# akabeacon_square_type2.net
KiCad netlist of a schematic drawn in EAGLE
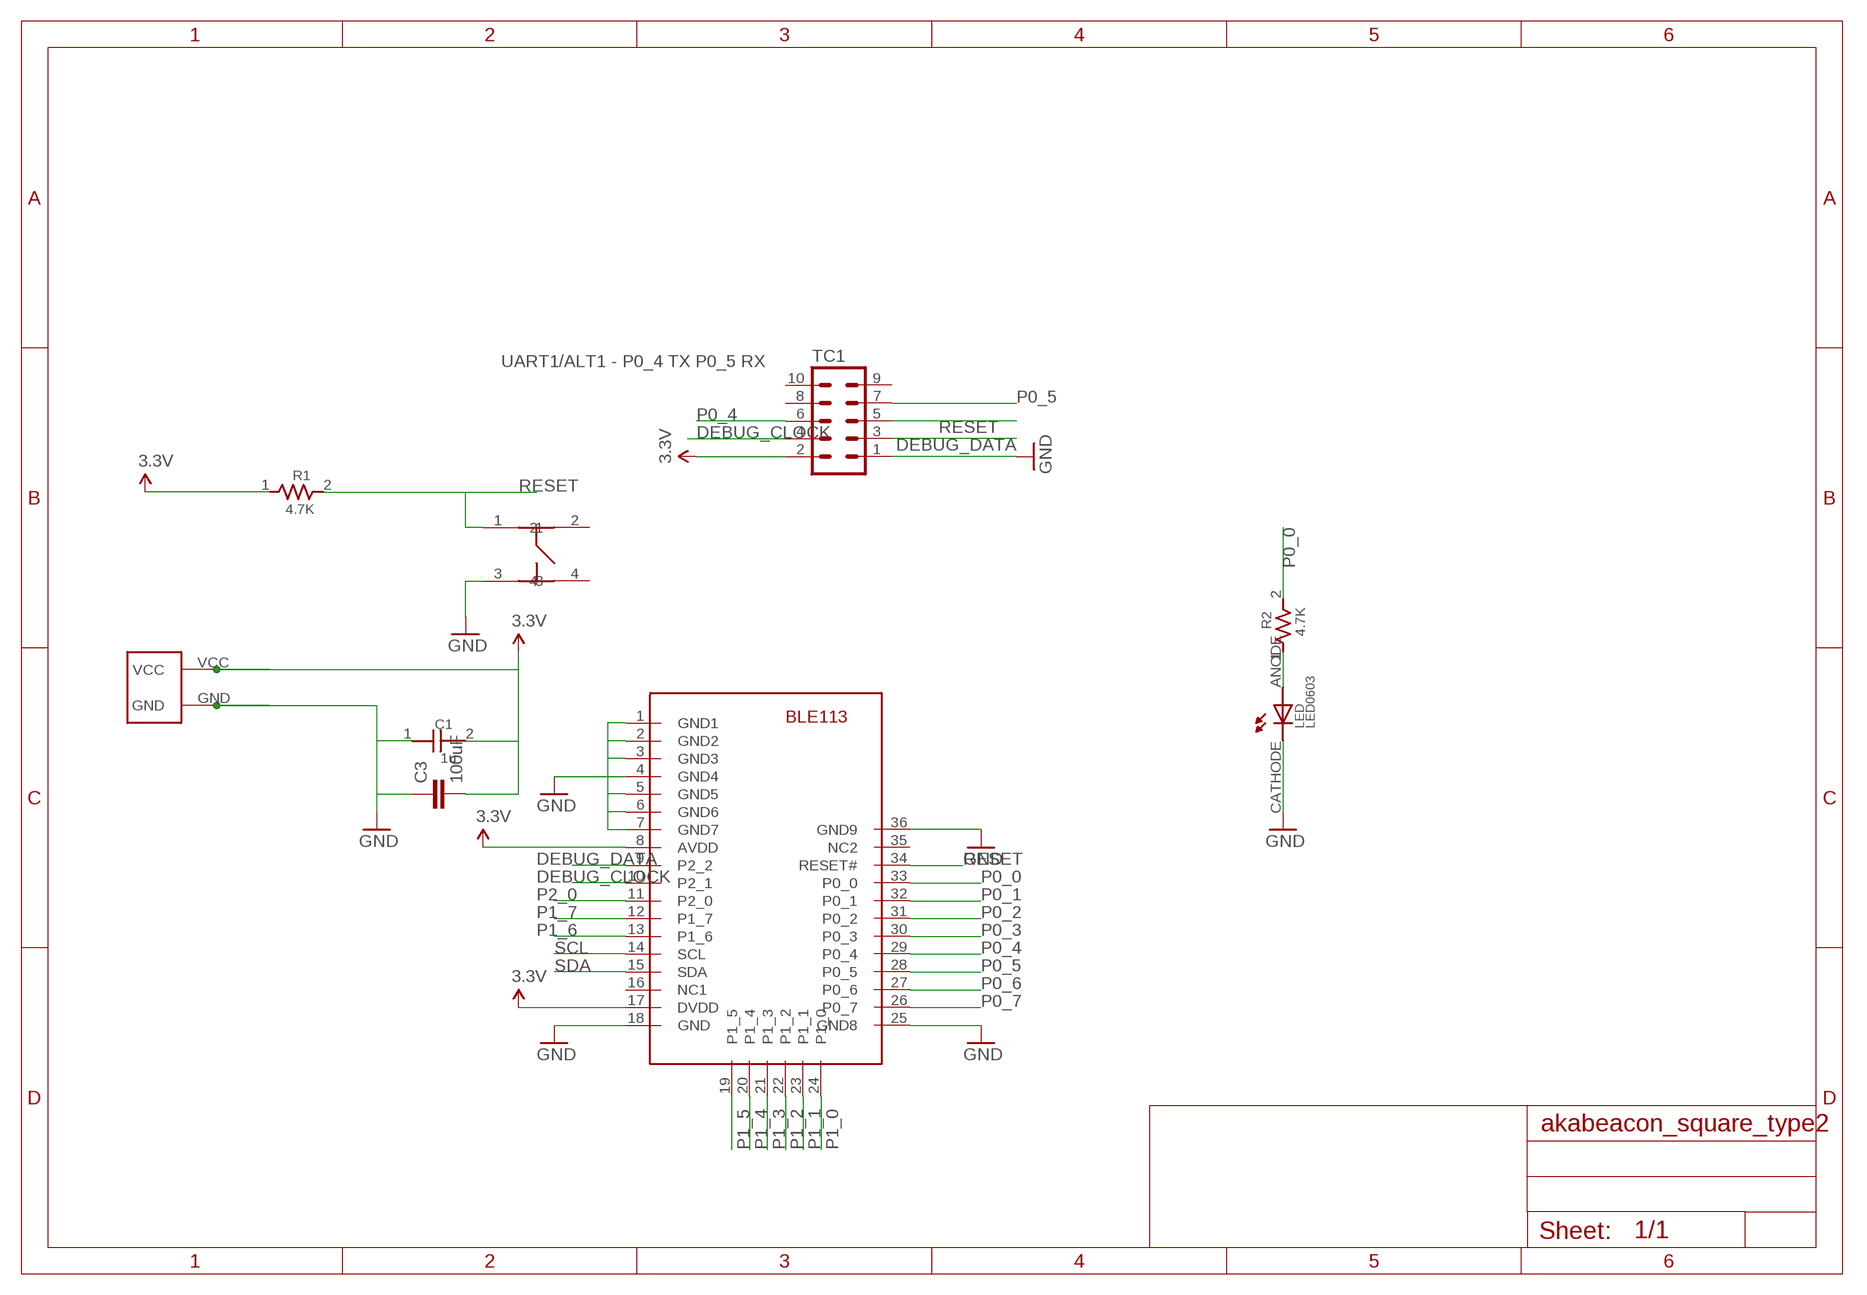
[diagram p0: schematic, sheet 1]

(export (version "E")
  (design (tool "Eeschema 10.0.6"))
  (components
    (comp (ref "C1")
      (value "1u")
      (footprint "eagle-import:0603")
      (libsource (lib "eagle-import") (part "CAPACITOR0603"))
    )
    (comp (ref "C3")
      (value "100uF")
      (footprint "eagle-import:1206")
      (libsource (lib "eagle-import") (part "10UF-6.3V-20%(1206)"))
    )
    (comp (ref "LED")
      (value "LED0603")
      (footprint "eagle-import:0603")
      (libsource (lib "eagle-import") (part "LED0603"))
    )
    (comp (ref "R1")
      (value "4.7K")
      (footprint "eagle-import:0603")
      (libsource (lib "eagle-import") (part "RESISTOR0603"))
    )
    (comp (ref "R2")
      (value "4.7K")
      (footprint "eagle-import:0603")
      (libsource (lib "eagle-import") (part "RESISTOR0603"))
    )
    (comp (ref "TC1")
      (value "TC2050-IDC-NL")
      (footprint "eagle-import:TC2050-IDC-NL")
      (libsource (lib "eagle-import") (part "TC2050-IDC-NL"))
    )
    (comp (ref "U$3")
      (value "SQUARE-TYPE2-TC2050")
      (footprint "eagle-import:SQUARE-TYPE2-TC2050")
      (libsource (lib "eagle-import") (part "SQUARE-TYPE2-TC2050"))
    )
    (comp (ref "U$5")
      (value "BLE113")
      (footprint "eagle-import:BLE113")
      (libsource (lib "eagle-import") (part "BLE113"))
    )
    (comp (ref "U$6")
      (value "SWICTH-4P(KMR2)")
      (footprint "eagle-import:SWITCH-4P(KMR2)")
      (libsource (lib "eagle-import") (part "SWICTH-4P(KMR2)"))
    )
  )
  (nets
    (net (code "1") (name "/DEBUG_CLOCK") (class "Default")
      (node (ref "TC1") (pin "4") (pinfunction "4_4") (pintype "passive"))
      (node (ref "U$5") (pin "10") (pinfunction "P2_1_10") (pintype "bidirectional"))
    )
    (net (code "2") (name "/DEBUG_DATA") (class "Default")
      (node (ref "TC1") (pin "3") (pinfunction "3_3") (pintype "passive"))
      (node (ref "U$5") (pin "9") (pinfunction "P2_2_9") (pintype "bidirectional"))
    )
    (net (code "3") (name "/P0_0") (class "Default")
      (node (ref "R2") (pin "2") (pinfunction "2_2") (pintype "passive"))
      (node (ref "U$5") (pin "33") (pinfunction "P0_0_33") (pintype "bidirectional"))
    )
    (net (code "4") (name "/P0_1") (class "Default")
      (node (ref "U$5") (pin "32") (pinfunction "P0_1_32") (pintype "bidirectional"))
    )
    (net (code "5") (name "/P0_2") (class "Default")
      (node (ref "U$5") (pin "31") (pinfunction "P0_2_31") (pintype "bidirectional"))
    )
    (net (code "6") (name "/P0_3") (class "Default")
      (node (ref "U$5") (pin "30") (pinfunction "P0_3_30") (pintype "bidirectional"))
    )
    (net (code "7") (name "/P0_4") (class "Default")
      (node (ref "TC1") (pin "6") (pinfunction "6_6") (pintype "passive"))
      (node (ref "U$5") (pin "29") (pinfunction "P0_4_29") (pintype "bidirectional"))
    )
    (net (code "8") (name "/P0_5") (class "Default")
      (node (ref "TC1") (pin "7") (pinfunction "7_7") (pintype "passive"))
      (node (ref "U$5") (pin "28") (pinfunction "P0_5_28") (pintype "bidirectional"))
    )
    (net (code "9") (name "/P0_6") (class "Default")
      (node (ref "U$5") (pin "27") (pinfunction "P0_6_27") (pintype "bidirectional"))
    )
    (net (code "10") (name "/P0_7") (class "Default")
      (node (ref "U$5") (pin "26") (pinfunction "P0_7_26") (pintype "bidirectional"))
    )
    (net (code "11") (name "/P1_0") (class "Default")
      (node (ref "U$5") (pin "24") (pinfunction "P1_0_24") (pintype "bidirectional"))
    )
    (net (code "12") (name "/P1_1") (class "Default")
      (node (ref "U$5") (pin "23") (pinfunction "P1_1_23") (pintype "bidirectional"))
    )
    (net (code "13") (name "/P1_2") (class "Default")
      (node (ref "U$5") (pin "22") (pinfunction "P1_2_22") (pintype "bidirectional"))
    )
    (net (code "14") (name "/P1_3") (class "Default")
      (node (ref "U$5") (pin "21") (pinfunction "P1_3_21") (pintype "bidirectional"))
    )
    (net (code "15") (name "/P1_4") (class "Default")
      (node (ref "U$5") (pin "20") (pinfunction "P1_4_20") (pintype "bidirectional"))
    )
    (net (code "16") (name "/P1_5") (class "Default")
      (node (ref "U$5") (pin "19") (pinfunction "P1_5_19") (pintype "bidirectional"))
    )
    (net (code "17") (name "/P1_6") (class "Default")
      (node (ref "U$5") (pin "13") (pinfunction "P1_6_13") (pintype "bidirectional"))
    )
    (net (code "18") (name "/P1_7") (class "Default")
      (node (ref "U$5") (pin "12") (pinfunction "P1_7_12") (pintype "bidirectional"))
    )
    (net (code "19") (name "/P2_0") (class "Default")
      (node (ref "U$5") (pin "11") (pinfunction "P2_0_11") (pintype "bidirectional"))
    )
    (net (code "20") (name "/RESET") (class "Default")
      (node (ref "R1") (pin "2") (pinfunction "2_2") (pintype "passive"))
      (node (ref "TC1") (pin "5") (pinfunction "5_5") (pintype "passive"))
      (node (ref "U$5") (pin "34") (pinfunction "RESET#_34") (pintype "bidirectional"))
      (node (ref "U$6") (pin "1") (pinfunction "1_1") (pintype "bidirectional"))
    )
    (net (code "21") (name "/SCL") (class "Default")
      (node (ref "U$5") (pin "14") (pinfunction "SCL_14") (pintype "bidirectional"))
    )
    (net (code "22") (name "/SDA") (class "Default")
      (node (ref "U$5") (pin "15") (pinfunction "SDA_15") (pintype "bidirectional"))
    )
    (net (code "23") (name "3.3V") (class "Default")
      (node (ref "C1") (pin "2") (pinfunction "2_2") (pintype "passive"))
      (node (ref "C3") (pin "2") (pinfunction "2_2") (pintype "passive"))
      (node (ref "R1") (pin "1") (pinfunction "1_1") (pintype "passive"))
      (node (ref "TC1") (pin "2") (pinfunction "2_2") (pintype "passive"))
      (node (ref "U$3") (pin "VCC") (pinfunction "VCC_VCC") (pintype "bidirectional"))
      (node (ref "U$5") (pin "17") (pinfunction "DVDD_17") (pintype "bidirectional"))
      (node (ref "U$5") (pin "8") (pinfunction "AVDD_8") (pintype "bidirectional"))
    )
    (net (code "24") (name "GND") (class "Default")
      (node (ref "C1") (pin "1") (pinfunction "1_1") (pintype "passive"))
      (node (ref "C3") (pin "1") (pinfunction "1_1") (pintype "passive"))
      (node (ref "LED") (pin "CATHODE") (pinfunction "CATHODE_CATHODE") (pintype "passive"))
      (node (ref "TC1") (pin "1") (pinfunction "1_1") (pintype "passive"))
      (node (ref "U$3") (pin "GND") (pinfunction "GND_GND") (pintype "bidirectional"))
      (node (ref "U$5") (pin "1") (pinfunction "GND1_1") (pintype "bidirectional"))
      (node (ref "U$5") (pin "18") (pinfunction "GND_18") (pintype "bidirectional"))
      (node (ref "U$5") (pin "2") (pinfunction "GND2_2") (pintype "bidirectional"))
      (node (ref "U$5") (pin "25") (pinfunction "GND8_25") (pintype "bidirectional"))
      (node (ref "U$5") (pin "3") (pinfunction "GND3_3") (pintype "bidirectional"))
      (node (ref "U$5") (pin "36") (pinfunction "GND9_36") (pintype "bidirectional"))
      (node (ref "U$5") (pin "4") (pinfunction "GND4_4") (pintype "bidirectional"))
      (node (ref "U$5") (pin "5") (pinfunction "GND5_5") (pintype "bidirectional"))
      (node (ref "U$5") (pin "6") (pinfunction "GND6_6") (pintype "bidirectional"))
      (node (ref "U$5") (pin "7") (pinfunction "GND7_7") (pintype "bidirectional"))
      (node (ref "U$6") (pin "3") (pinfunction "3_3") (pintype "bidirectional"))
    )
    (net (code "25") (name "Net-(LED-PadANODE)") (class "Default")
      (node (ref "LED") (pin "ANODE") (pinfunction "ANODE_ANODE") (pintype "passive"))
      (node (ref "R2") (pin "1") (pinfunction "1_1") (pintype "passive"))
    )
    (net (code "26") (name "unconnected-(TC1-Pad8)") (class "Default")
      (node (ref "TC1") (pin "8") (pinfunction "8_8") (pintype "passive"))
    )
    (net (code "27") (name "unconnected-(TC1-Pad9)") (class "Default")
      (node (ref "TC1") (pin "9") (pinfunction "9_9") (pintype "passive"))
    )
    (net (code "28") (name "unconnected-(TC1-Pad10)") (class "Default")
      (node (ref "TC1") (pin "10") (pinfunction "10_10") (pintype "passive"))
    )
    (net (code "29") (name "unconnected-(U$5-NC1-Pad16)") (class "Default")
      (node (ref "U$5") (pin "16") (pinfunction "NC1_16") (pintype "bidirectional"))
    )
    (net (code "30") (name "unconnected-(U$5-NC2-Pad35)") (class "Default")
      (node (ref "U$5") (pin "35") (pinfunction "NC2_35") (pintype "bidirectional"))
    )
    (net (code "31") (name "unconnected-(U$6-Pad2)") (class "Default")
      (node (ref "U$6") (pin "2") (pinfunction "2_2") (pintype "bidirectional"))
    )
    (net (code "32") (name "unconnected-(U$6-Pad4)") (class "Default")
      (node (ref "U$6") (pin "4") (pinfunction "4_4") (pintype "bidirectional"))
    )
  )
)
